# gyro_board.net
KiCad netlist of a schematic drawn in EAGLE
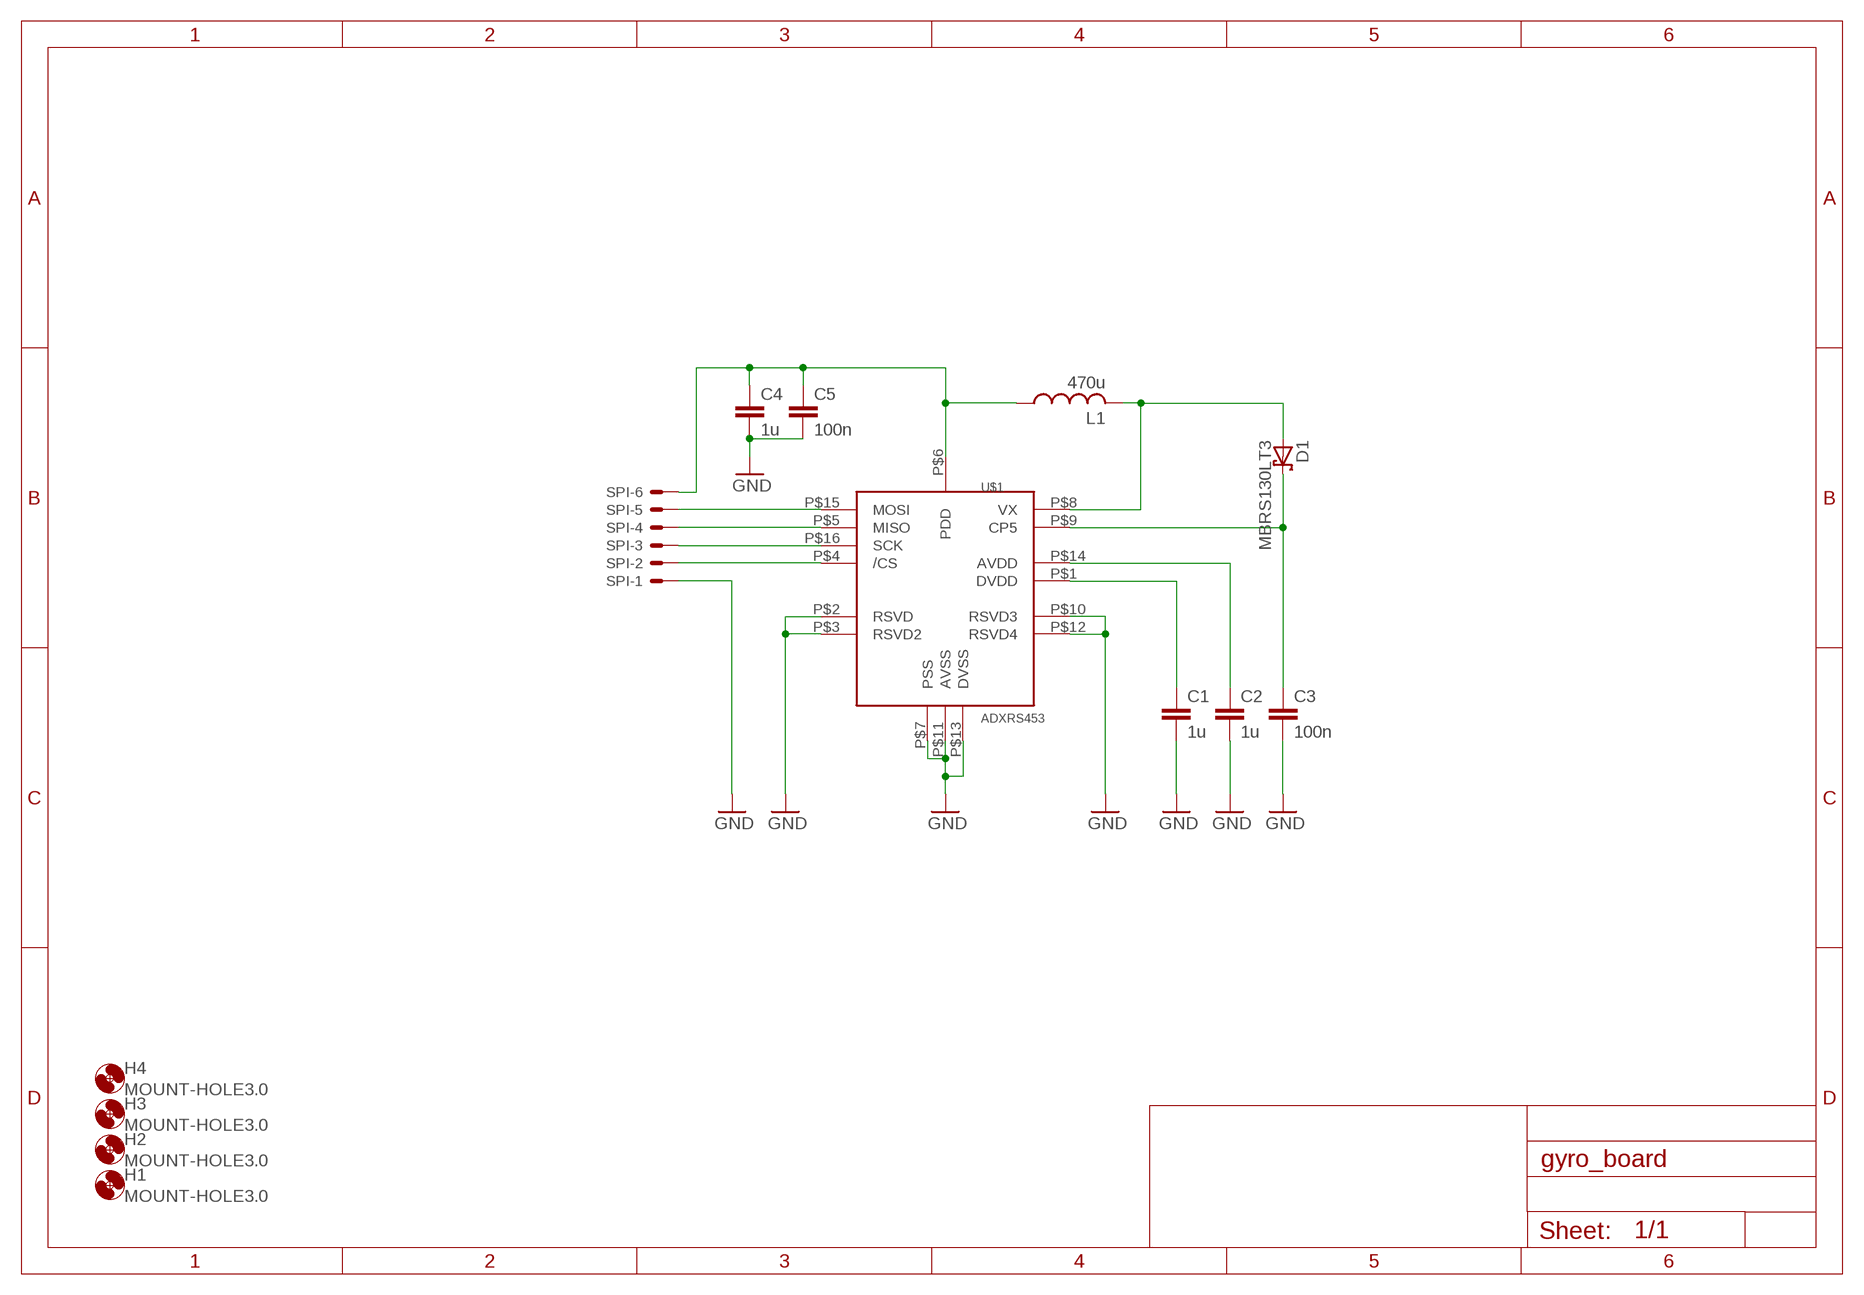
[diagram p0: schematic, sheet 1]

(export (version "E")
  (design (tool "Eeschema 10.0.6"))
  (components
    (comp (ref "C1")
      (value "1u")
      (footprint "eagle-import:C0603")
      (libsource (lib "eagle-import") (part "C-EUC0603"))
    )
    (comp (ref "C2")
      (value "1u")
      (footprint "eagle-import:C0603")
      (libsource (lib "eagle-import") (part "C-EUC0603"))
    )
    (comp (ref "C3")
      (value "100n")
      (footprint "eagle-import:C0603")
      (libsource (lib "eagle-import") (part "C-EUC0603"))
    )
    (comp (ref "C4")
      (value "1u")
      (footprint "eagle-import:C0603")
      (libsource (lib "eagle-import") (part "C-EUC0603"))
    )
    (comp (ref "C5")
      (value "100n")
      (footprint "eagle-import:C0603")
      (libsource (lib "eagle-import") (part "C-EUC0603"))
    )
    (comp (ref "D1")
      (value "MBRS130LT3")
      (footprint "eagle-import:SMB")
      (libsource (lib "eagle-import") (part "MBRS130LT3"))
    )
    (comp (ref "H1")
      (value "MOUNT-HOLE3.0")
      (footprint "eagle-import:3,0")
      (libsource (lib "eagle-import") (part "MOUNT-HOLE3.0"))
    )
    (comp (ref "H2")
      (value "MOUNT-HOLE3.0")
      (footprint "eagle-import:3,0")
      (libsource (lib "eagle-import") (part "MOUNT-HOLE3.0"))
    )
    (comp (ref "H3")
      (value "MOUNT-HOLE3.0")
      (footprint "eagle-import:3,0")
      (libsource (lib "eagle-import") (part "MOUNT-HOLE3.0"))
    )
    (comp (ref "H4")
      (value "MOUNT-HOLE3.0")
      (footprint "eagle-import:3,0")
      (libsource (lib "eagle-import") (part "MOUNT-HOLE3.0"))
    )
    (comp (ref "L1")
      (value "470u")
      (footprint "eagle-import:L1812")
      (libsource (lib "eagle-import") (part "L-USL1812"))
    )
    (comp (ref "SPI")
      (value "22-23-2061")
      (footprint "eagle-import:22-23-2061")
      (fields (field (name "MF") "MOLEX"))
      (libsource (lib "eagle-import") (part "22-23-2061"))
    )
    (comp (ref "U$1")
      (value "ADXRS453")
      (footprint "eagle-import:SOIC_CAV")
      (libsource (lib "eagle-import") (part "ADXRS453"))
    )
  )
  (nets
    (net (code "1") (name "GND") (class "Default")
      (node (ref "C1") (pin "2") (pinfunction "2_2") (pintype "passive"))
      (node (ref "C2") (pin "2") (pinfunction "2_2") (pintype "passive"))
      (node (ref "C3") (pin "2") (pinfunction "2_2") (pintype "passive"))
      (node (ref "C4") (pin "2") (pinfunction "2_2") (pintype "passive"))
      (node (ref "C5") (pin "2") (pinfunction "2_2") (pintype "passive"))
      (node (ref "SPI") (pin "1") (pinfunction "S_1") (pintype "passive"))
      (node (ref "U$1") (pin "P$10") (pinfunction "RSVD3_P$10") (pintype "bidirectional"))
      (node (ref "U$1") (pin "P$11") (pinfunction "AVSS_P$11") (pintype "bidirectional"))
      (node (ref "U$1") (pin "P$12") (pinfunction "RSVD4_P$12") (pintype "bidirectional"))
      (node (ref "U$1") (pin "P$13") (pinfunction "DVSS_P$13") (pintype "bidirectional"))
      (node (ref "U$1") (pin "P$2") (pinfunction "RSVD_P$2") (pintype "bidirectional"))
      (node (ref "U$1") (pin "P$3") (pinfunction "RSVD2_P$3") (pintype "bidirectional"))
      (node (ref "U$1") (pin "P$7") (pinfunction "PSS_P$7") (pintype "bidirectional"))
    )
    (net (code "2") (name "Net-(SPIB-S)") (class "Default")
      (node (ref "SPI") (pin "2") (pinfunction "S_2") (pintype "passive"))
      (node (ref "U$1") (pin "P$4") (pinfunction "/CS_P$4") (pintype "bidirectional"))
    )
    (net (code "3") (name "Net-(SPIC-S)") (class "Default")
      (node (ref "SPI") (pin "3") (pinfunction "S_3") (pintype "passive"))
      (node (ref "U$1") (pin "P$16") (pinfunction "SCK_P$16") (pintype "bidirectional"))
    )
    (net (code "4") (name "Net-(SPID-S)") (class "Default")
      (node (ref "SPI") (pin "4") (pinfunction "S_4") (pintype "passive"))
      (node (ref "U$1") (pin "P$5") (pinfunction "MISO_P$5") (pintype "bidirectional"))
    )
    (net (code "5") (name "Net-(SPIE-S)") (class "Default")
      (node (ref "SPI") (pin "5") (pinfunction "S_5") (pintype "passive"))
      (node (ref "U$1") (pin "P$15") (pinfunction "MOSI_P$15") (pintype "bidirectional"))
    )
    (net (code "6") (name "Net-(SPIF-S)") (class "Default")
      (node (ref "C4") (pin "1") (pinfunction "1_1") (pintype "passive"))
      (node (ref "C5") (pin "1") (pinfunction "1_1") (pintype "passive"))
      (node (ref "L1") (pin "1") (pinfunction "1_1") (pintype "passive"))
      (node (ref "SPI") (pin "6") (pinfunction "S_6") (pintype "passive"))
      (node (ref "U$1") (pin "P$6") (pinfunction "PDD_P$6") (pintype "bidirectional"))
    )
    (net (code "7") (name "Net-(U$1-AVDD)") (class "Default")
      (node (ref "C2") (pin "1") (pinfunction "1_1") (pintype "passive"))
      (node (ref "U$1") (pin "P$14") (pinfunction "AVDD_P$14") (pintype "bidirectional"))
    )
    (net (code "8") (name "Net-(U$1-CP5)") (class "Default")
      (node (ref "C3") (pin "1") (pinfunction "1_1") (pintype "passive"))
      (node (ref "D1") (pin "C") (pinfunction "C_C") (pintype "passive"))
      (node (ref "U$1") (pin "P$9") (pinfunction "CP5_P$9") (pintype "bidirectional"))
    )
    (net (code "9") (name "Net-(U$1-DVDD)") (class "Default")
      (node (ref "C1") (pin "1") (pinfunction "1_1") (pintype "passive"))
      (node (ref "U$1") (pin "P$1") (pinfunction "DVDD_P$1") (pintype "bidirectional"))
    )
    (net (code "10") (name "Net-(U$1-VX)") (class "Default")
      (node (ref "D1") (pin "A") (pinfunction "A_A") (pintype "passive"))
      (node (ref "L1") (pin "2") (pinfunction "2_2") (pintype "passive"))
      (node (ref "U$1") (pin "P$8") (pinfunction "VX_P$8") (pintype "bidirectional"))
    )
  )
)
